# audible.net
KiCad netlist of a schematic drawn in EAGLE
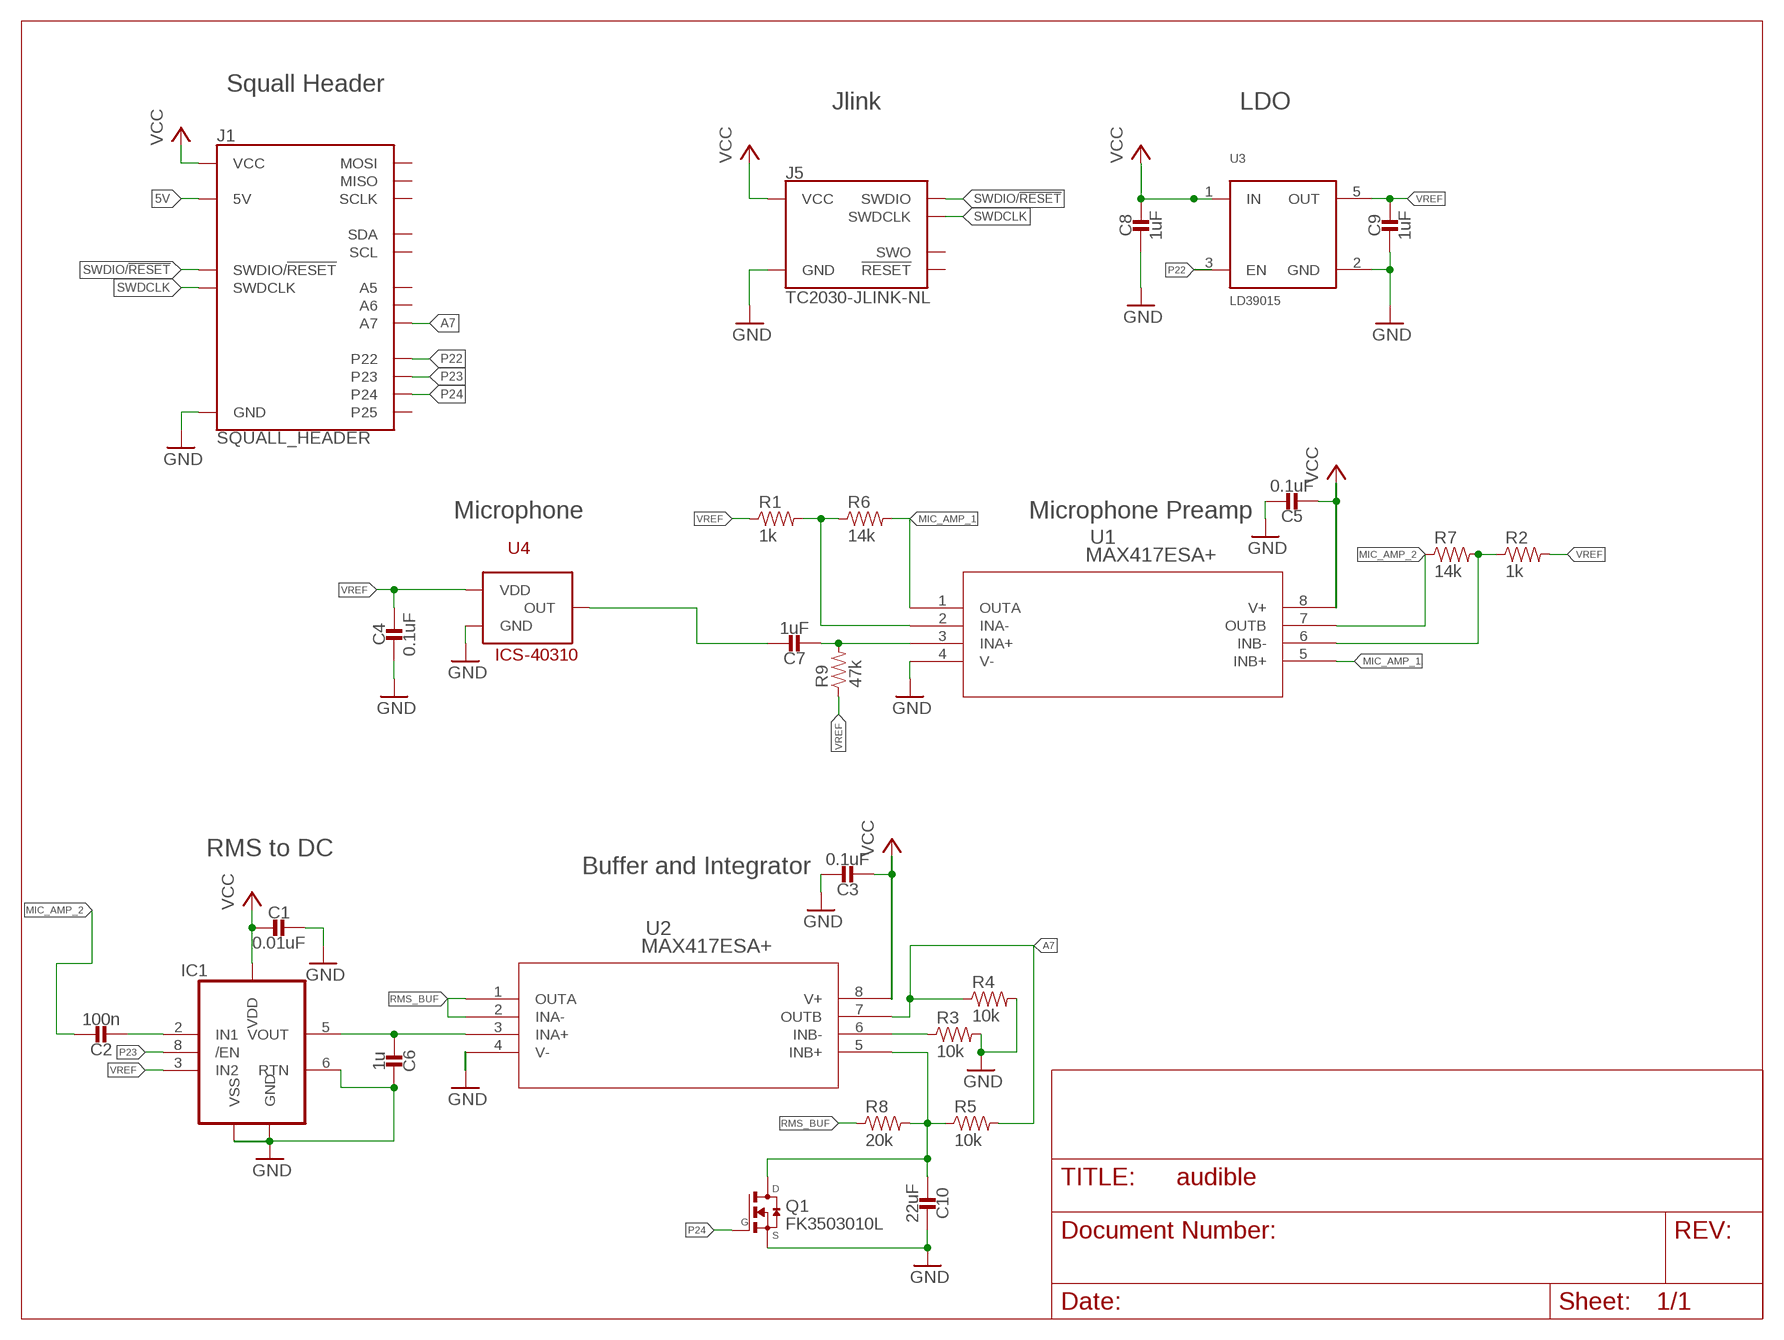
[diagram p0: schematic, sheet 1]

(export (version "E")
  (design (tool "Eeschema 10.0.6"))
  (components
    (comp (ref "C1")
      (value "0.01uF")
      (footprint "eagle-import:0402_CAP")
      (libsource (lib "eagle-import") (part "CAPACITOR"))
    )
    (comp (ref "C2")
      (value "100n")
      (footprint "eagle-import:0402_CAP")
      (libsource (lib "eagle-import") (part "CAPACITOR"))
    )
    (comp (ref "C3")
      (value "0.1uF")
      (footprint "eagle-import:0402_CAP")
      (libsource (lib "eagle-import") (part "CAPACITOR"))
    )
    (comp (ref "C4")
      (value "0.1uF")
      (footprint "eagle-import:0402_CAP")
      (libsource (lib "eagle-import") (part "CAPACITOR"))
    )
    (comp (ref "C5")
      (value "0.1uF")
      (footprint "eagle-import:0402_CAP")
      (libsource (lib "eagle-import") (part "CAPACITOR"))
    )
    (comp (ref "C6")
      (value "1u")
      (footprint "eagle-import:0402_CAP")
      (libsource (lib "eagle-import") (part "CAPACITOR"))
    )
    (comp (ref "C7")
      (value "1uF")
      (footprint "eagle-import:0402_CAP")
      (libsource (lib "eagle-import") (part "CAPACITOR"))
    )
    (comp (ref "C8")
      (value "1uF")
      (footprint "eagle-import:0402_CAP")
      (libsource (lib "eagle-import") (part "CAPACITOR"))
    )
    (comp (ref "C9")
      (value "1uF")
      (footprint "eagle-import:0402_CAP")
      (libsource (lib "eagle-import") (part "CAPACITOR"))
    )
    (comp (ref "C10")
      (value "22uF")
      (footprint "eagle-import:0402_CAP")
      (libsource (lib "eagle-import") (part "CAPACITOR"))
    )
    (comp (ref "IC1")
      (value "LTC1966CMS8")
      (footprint "eagle-import:MSOP8")
      (libsource (lib "eagle-import") (part "LTC1966MS8C"))
    )
    (comp (ref "J1")
      (value "SQUALL_HEADER")
      (footprint "eagle-import:SQUALL_HEADER")
      (libsource (lib "eagle-import") (part "SQUALL_HEADER"))
    )
    (comp (ref "J5")
      (value "TC2030-JLINK-NL")
      (footprint "eagle-import:TC2030-IDC-NL")
      (libsource (lib "eagle-import") (part "TC2030-JLINK-NL"))
    )
    (comp (ref "Q1")
      (value "FK3503010L")
      (footprint "eagle-import:SC85")
      (libsource (lib "eagle-import") (part "FK3503010L"))
    )
    (comp (ref "R1")
      (value "1k")
      (footprint "eagle-import:0402_RES")
      (libsource (lib "eagle-import") (part "RESISTOR0402_RES"))
    )
    (comp (ref "R2")
      (value "1k")
      (footprint "eagle-import:0402_RES")
      (libsource (lib "eagle-import") (part "RESISTOR0402_RES"))
    )
    (comp (ref "R3")
      (value "10k")
      (footprint "eagle-import:0402_RES")
      (libsource (lib "eagle-import") (part "RESISTOR0402_RES"))
    )
    (comp (ref "R4")
      (value "10k")
      (footprint "eagle-import:0402_RES")
      (libsource (lib "eagle-import") (part "RESISTOR0402_RES"))
    )
    (comp (ref "R5")
      (value "10k")
      (footprint "eagle-import:0402_RES")
      (libsource (lib "eagle-import") (part "RESISTOR0402_RES"))
    )
    (comp (ref "R6")
      (value "14k")
      (footprint "eagle-import:0402_RES")
      (libsource (lib "eagle-import") (part "RESISTOR0402_RES"))
    )
    (comp (ref "R7")
      (value "14k")
      (footprint "eagle-import:0402_RES")
      (libsource (lib "eagle-import") (part "RESISTOR0402_RES"))
    )
    (comp (ref "R8")
      (value "20k")
      (footprint "eagle-import:0402_RES")
      (libsource (lib "eagle-import") (part "RESISTOR0402_RES"))
    )
    (comp (ref "R9")
      (value "47k")
      (footprint "eagle-import:0402_RES")
      (libsource (lib "eagle-import") (part "RESISTOR0402_RES"))
    )
    (comp (ref "U1")
      (value "MAX417ESA+")
      (footprint "eagle-import:21-0041B_8")
      (fields (field (name "MANUFACTURER_PART_NUMBER") "max417esa+"))
      (libsource (lib "eagle-import") (part "MAX417ESA+"))
    )
    (comp (ref "U2")
      (value "MAX417ESA+")
      (footprint "eagle-import:21-0041B_8")
      (fields (field (name "MANUFACTURER_PART_NUMBER") "max417esa+"))
      (libsource (lib "eagle-import") (part "MAX417ESA+"))
    )
    (comp (ref "U3")
      (value "LD39015")
      (footprint "eagle-import:SOT-23-5")
      (libsource (lib "eagle-import") (part "LD39015"))
    )
    (comp (ref "U4")
      (value "ICS-40310")
      (footprint "eagle-import:LGA_CAV3")
      (libsource (lib "eagle-import") (part "ICS-40310"))
    )
  )
  (nets
    (net (code "1") (name "/SWDIO{slash}~{RESET}") (class "Default")
      (node (ref "J1") (pin "B4") (pinfunction "SWDIO/~{RESET}_B4") (pintype "bidirectional"))
      (node (ref "J5") (pin "2") (pinfunction "SWDIO_2") (pintype "bidirectional"))
    )
    (net (code "2") (name "5V") (class "Default")
      (node (ref "J1") (pin "A5") (pinfunction "5V_A5") (pintype "bidirectional"))
      (node (ref "J1") (pin "A7") (pinfunction "5V_A7") (pintype "bidirectional"))
    )
    (net (code "3") (name "A7") (class "Default")
      (node (ref "J1") (pin "B5") (pinfunction "A7_B5") (pintype "bidirectional"))
      (node (ref "R4") (pin "1") (pinfunction "1_1") (pintype "passive"))
      (node (ref "R5") (pin "2") (pinfunction "2_2") (pintype "passive"))
      (node (ref "U2") (pin "7") (pinfunction "OUTB_7") (pintype "output"))
    )
    (net (code "4") (name "GND") (class "Default")
      (node (ref "C1") (pin "1") (pinfunction "1_1") (pintype "bidirectional"))
      (node (ref "C10") (pin "1") (pinfunction "1_1") (pintype "bidirectional"))
      (node (ref "C3") (pin "1") (pinfunction "1_1") (pintype "bidirectional"))
      (node (ref "C4") (pin "2") (pinfunction "2_2") (pintype "bidirectional"))
      (node (ref "C5") (pin "1") (pinfunction "1_1") (pintype "bidirectional"))
      (node (ref "C6") (pin "1") (pinfunction "1_1") (pintype "bidirectional"))
      (node (ref "C8") (pin "2") (pinfunction "2_2") (pintype "bidirectional"))
      (node (ref "C9") (pin "2") (pinfunction "2_2") (pintype "bidirectional"))
      (node (ref "IC1") (pin "1") (pinfunction "GND_1") (pintype "bidirectional"))
      (node (ref "IC1") (pin "4") (pinfunction "VSS_4") (pintype "bidirectional"))
      (node (ref "IC1") (pin "6") (pinfunction "RTN_6") (pintype "passive"))
      (node (ref "J1") (pin "A10") (pinfunction "GND_A10") (pintype "bidirectional"))
      (node (ref "J1") (pin "A9") (pinfunction "GND_A9") (pintype "bidirectional"))
      (node (ref "J5") (pin "5") (pinfunction "GND_5") (pintype "bidirectional"))
      (node (ref "Q1") (pin "2") (pinfunction "S_2") (pintype "passive"))
      (node (ref "R3") (pin "2") (pinfunction "2_2") (pintype "passive"))
      (node (ref "R4") (pin "2") (pinfunction "2_2") (pintype "passive"))
      (node (ref "U1") (pin "4") (pinfunction "V-_4") (pintype "power_in"))
      (node (ref "U2") (pin "4") (pinfunction "V-_4") (pintype "power_in"))
      (node (ref "U3") (pin "2") (pinfunction "GND_2") (pintype "bidirectional"))
      (node (ref "U4") (pin "P$2") (pinfunction "GND_P$2") (pintype "bidirectional"))
    )
    (net (code "5") (name "MIC_AMP_1") (class "Default")
      (node (ref "R6") (pin "2") (pinfunction "2_2") (pintype "passive"))
      (node (ref "U1") (pin "1") (pinfunction "OUTA_1") (pintype "output"))
      (node (ref "U1") (pin "5") (pinfunction "INB+_5") (pintype "input"))
    )
    (net (code "6") (name "MIC_AMP_2") (class "Default")
      (node (ref "C2") (pin "1") (pinfunction "1_1") (pintype "bidirectional"))
      (node (ref "R7") (pin "1") (pinfunction "1_1") (pintype "passive"))
      (node (ref "U1") (pin "7") (pinfunction "OUTB_7") (pintype "output"))
    )
    (net (code "7") (name "Net-(IC1-IN1)") (class "Default")
      (node (ref "C2") (pin "2") (pinfunction "2_2") (pintype "bidirectional"))
      (node (ref "IC1") (pin "2") (pinfunction "IN1_2") (pintype "input"))
    )
    (net (code "8") (name "Net-(IC1-VOUT)") (class "Default")
      (node (ref "C6") (pin "2") (pinfunction "2_2") (pintype "bidirectional"))
      (node (ref "IC1") (pin "5") (pinfunction "VOUT_5") (pintype "output"))
      (node (ref "U2") (pin "3") (pinfunction "INA+_3") (pintype "input"))
    )
    (net (code "9") (name "Net-(Q1-D)") (class "Default")
      (node (ref "C10") (pin "2") (pinfunction "2_2") (pintype "bidirectional"))
      (node (ref "Q1") (pin "3") (pinfunction "D_3") (pintype "passive"))
      (node (ref "R5") (pin "1") (pinfunction "1_1") (pintype "passive"))
      (node (ref "R8") (pin "2") (pinfunction "2_2") (pintype "passive"))
      (node (ref "U2") (pin "5") (pinfunction "INB+_5") (pintype "input"))
    )
    (net (code "10") (name "Net-(U1-INA+)") (class "Default")
      (node (ref "C7") (pin "2") (pinfunction "2_2") (pintype "bidirectional"))
      (node (ref "R9") (pin "2") (pinfunction "2_2") (pintype "passive"))
      (node (ref "U1") (pin "3") (pinfunction "INA+_3") (pintype "input"))
    )
    (net (code "11") (name "Net-(U1-INA-)") (class "Default")
      (node (ref "R1") (pin "2") (pinfunction "2_2") (pintype "passive"))
      (node (ref "R6") (pin "1") (pinfunction "1_1") (pintype "passive"))
      (node (ref "U1") (pin "2") (pinfunction "INA-_2") (pintype "input"))
    )
    (net (code "12") (name "Net-(U1-INB-)") (class "Default")
      (node (ref "R2") (pin "1") (pinfunction "1_1") (pintype "passive"))
      (node (ref "R7") (pin "2") (pinfunction "2_2") (pintype "passive"))
      (node (ref "U1") (pin "6") (pinfunction "INB-_6") (pintype "input"))
    )
    (net (code "13") (name "Net-(U2-INB-)") (class "Default")
      (node (ref "R3") (pin "1") (pinfunction "1_1") (pintype "passive"))
      (node (ref "U2") (pin "6") (pinfunction "INB-_6") (pintype "input"))
    )
    (net (code "14") (name "Net-(U4-OUT)") (class "Default")
      (node (ref "C7") (pin "1") (pinfunction "1_1") (pintype "bidirectional"))
      (node (ref "U4") (pin "P$1") (pinfunction "OUT_P$1") (pintype "bidirectional"))
    )
    (net (code "15") (name "P22") (class "Default")
      (node (ref "J1") (pin "A2") (pinfunction "P22_A2") (pintype "bidirectional"))
      (node (ref "U3") (pin "3") (pinfunction "EN_3") (pintype "bidirectional"))
    )
    (net (code "16") (name "P23") (class "Default")
      (node (ref "IC1") (pin "8") (pinfunction "/EN_8") (pintype "input"))
      (node (ref "J1") (pin "A4") (pinfunction "P23_A4") (pintype "bidirectional"))
    )
    (net (code "17") (name "P24") (class "Default")
      (node (ref "J1") (pin "A6") (pinfunction "P24_A6") (pintype "bidirectional"))
      (node (ref "Q1") (pin "1") (pinfunction "G_1") (pintype "passive"))
    )
    (net (code "18") (name "RMS_BUF") (class "Default")
      (node (ref "R8") (pin "1") (pinfunction "1_1") (pintype "passive"))
      (node (ref "U2") (pin "1") (pinfunction "OUTA_1") (pintype "output"))
      (node (ref "U2") (pin "2") (pinfunction "INA-_2") (pintype "input"))
    )
    (net (code "19") (name "SWDCLK") (class "Default")
      (node (ref "J1") (pin "B2") (pinfunction "SWDCLK_B2") (pintype "bidirectional"))
      (node (ref "J5") (pin "4") (pinfunction "SWDCLK_4") (pintype "bidirectional"))
    )
    (net (code "20") (name "VCC") (class "Default")
      (node (ref "C1") (pin "2") (pinfunction "2_2") (pintype "bidirectional"))
      (node (ref "C3") (pin "2") (pinfunction "2_2") (pintype "bidirectional"))
      (node (ref "C5") (pin "2") (pinfunction "2_2") (pintype "bidirectional"))
      (node (ref "C8") (pin "1") (pinfunction "1_1") (pintype "bidirectional"))
      (node (ref "IC1") (pin "7") (pinfunction "VDD_7") (pintype "bidirectional"))
      (node (ref "J1") (pin "A1") (pinfunction "VCC_A1") (pintype "bidirectional"))
      (node (ref "J1") (pin "A3") (pinfunction "VCC_A3") (pintype "bidirectional"))
      (node (ref "J5") (pin "1") (pinfunction "VCC_1") (pintype "bidirectional"))
      (node (ref "U1") (pin "8") (pinfunction "V+_8") (pintype "power_in"))
      (node (ref "U2") (pin "8") (pinfunction "V+_8") (pintype "power_in"))
      (node (ref "U3") (pin "1") (pinfunction "IN_1") (pintype "bidirectional"))
    )
    (net (code "21") (name "VREF") (class "Default")
      (node (ref "C4") (pin "1") (pinfunction "1_1") (pintype "bidirectional"))
      (node (ref "C9") (pin "1") (pinfunction "1_1") (pintype "bidirectional"))
      (node (ref "IC1") (pin "3") (pinfunction "IN2_3") (pintype "input"))
      (node (ref "R1") (pin "1") (pinfunction "1_1") (pintype "passive"))
      (node (ref "R2") (pin "2") (pinfunction "2_2") (pintype "passive"))
      (node (ref "R9") (pin "1") (pinfunction "1_1") (pintype "passive"))
      (node (ref "U3") (pin "5") (pinfunction "OUT_5") (pintype "bidirectional"))
      (node (ref "U4") (pin "P$3") (pinfunction "VDD_P$3") (pintype "bidirectional"))
    )
    (net (code "22") (name "unconnected-(J1-A5-PadB9)") (class "Default")
      (node (ref "J1") (pin "B9") (pinfunction "A5_B9") (pintype "bidirectional"))
    )
    (net (code "23") (name "unconnected-(J1-A6-PadB7)") (class "Default")
      (node (ref "J1") (pin "B7") (pinfunction "A6_B7") (pintype "bidirectional"))
    )
    (net (code "24") (name "unconnected-(J1-MISO-PadB8)") (class "Default")
      (node (ref "J1") (pin "B8") (pinfunction "MISO_B8") (pintype "bidirectional"))
    )
    (net (code "25") (name "unconnected-(J1-MOSI-PadB6)") (class "Default")
      (node (ref "J1") (pin "B6") (pinfunction "MOSI_B6") (pintype "bidirectional"))
    )
    (net (code "26") (name "unconnected-(J1-P25-PadA8)") (class "Default")
      (node (ref "J1") (pin "A8") (pinfunction "P25_A8") (pintype "bidirectional"))
    )
    (net (code "27") (name "unconnected-(J1-SCL-PadB3)") (class "Default")
      (node (ref "J1") (pin "B3") (pinfunction "SCL_B3") (pintype "bidirectional"))
    )
    (net (code "28") (name "unconnected-(J1-SCLK-PadB10)") (class "Default")
      (node (ref "J1") (pin "B10") (pinfunction "SCLK_B10") (pintype "bidirectional"))
    )
    (net (code "29") (name "unconnected-(J1-SDA-PadB1)") (class "Default")
      (node (ref "J1") (pin "B1") (pinfunction "SDA_B1") (pintype "bidirectional"))
    )
    (net (code "30") (name "unconnected-(J5-SWO-Pad6)") (class "Default")
      (node (ref "J5") (pin "6") (pinfunction "SWO_6") (pintype "bidirectional"))
    )
    (net (code "31") (name "unconnected-(J5-~{RESET}-Pad3)") (class "Default")
      (node (ref "J5") (pin "3") (pinfunction "~{RESET}_3") (pintype "bidirectional"))
    )
  )
)
